# WeatherLightCoord.net
KiCad netlist of a schematic drawn in EAGLE
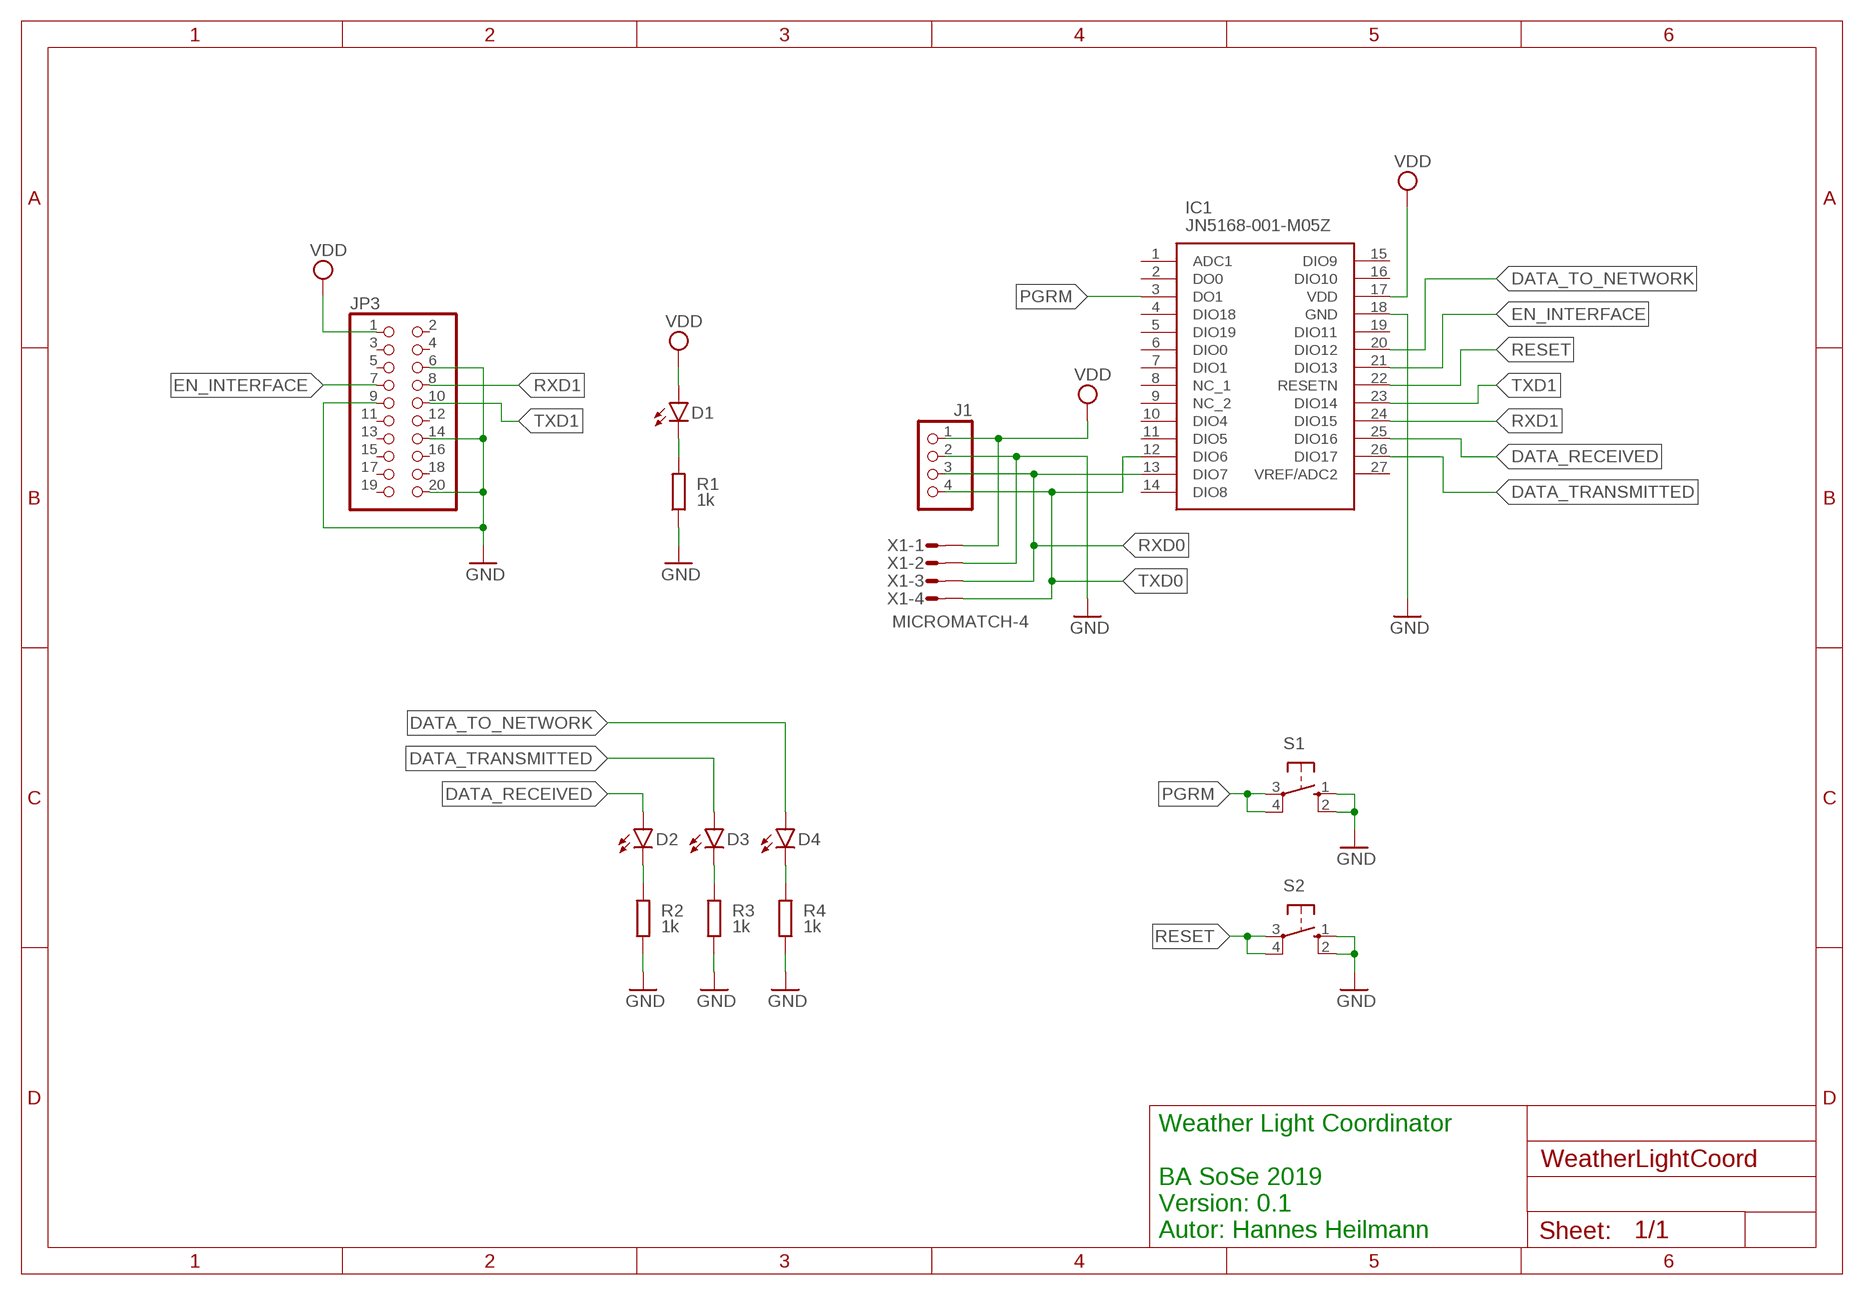
[diagram p0: schematic, sheet 1]

(export (version "E")
  (design (tool "Eeschema 10.0.6"))
  (components
    (comp (ref "D1")
      (value "LEDCHIPLED_1206")
      (footprint "eagle-import:CHIPLED_1206")
      (libsource (lib "eagle-import") (part "LEDCHIPLED_1206"))
    )
    (comp (ref "D2")
      (value "LEDCHIPLED_1206")
      (footprint "eagle-import:CHIPLED_1206")
      (libsource (lib "eagle-import") (part "LEDCHIPLED_1206"))
    )
    (comp (ref "D3")
      (value "LEDCHIPLED_1206")
      (footprint "eagle-import:CHIPLED_1206")
      (libsource (lib "eagle-import") (part "LEDCHIPLED_1206"))
    )
    (comp (ref "D4")
      (value "LEDCHIPLED_1206")
      (footprint "eagle-import:CHIPLED_1206")
      (libsource (lib "eagle-import") (part "LEDCHIPLED_1206"))
    )
    (comp (ref "IC1")
      (value "JN5168-001-M05Z")
      (footprint "eagle-import:JN5168001M05Z")
      (fields (field (name "MOUSER_PART_NUMBER") "771-JN5168-001-M05Z"))
      (libsource (lib "eagle-import") (part "JN5168-001-M05Z"))
    )
    (comp (ref "J1")
      (value "PINHD-1X4")
      (footprint "eagle-import:1X04")
      (libsource (lib "eagle-import") (part "PINHD-1X4"))
    )
    (comp (ref "JP3")
      (value "PINHD-2X10")
      (footprint "eagle-import:2X10")
      (libsource (lib "eagle-import") (part "PINHD-2X10"))
    )
    (comp (ref "R1")
      (value "1k")
      (footprint "eagle-import:R1206")
      (libsource (lib "eagle-import") (part "R-EU_R1206"))
    )
    (comp (ref "R2")
      (value "1k")
      (footprint "eagle-import:R1206")
      (libsource (lib "eagle-import") (part "R-EU_R1206"))
    )
    (comp (ref "R3")
      (value "1k")
      (footprint "eagle-import:R1206")
      (libsource (lib "eagle-import") (part "R-EU_R1206"))
    )
    (comp (ref "R4")
      (value "1k")
      (footprint "eagle-import:R1206")
      (libsource (lib "eagle-import") (part "R-EU_R1206"))
    )
    (comp (ref "S1")
      (value "10-XX")
      (footprint "eagle-import:B3F-10XX")
      (fields (field (name "MPN") "B3F-1000"))
      (libsource (lib "eagle-import") (part "10-XX"))
    )
    (comp (ref "S2")
      (value "10-XX")
      (footprint "eagle-import:B3F-10XX")
      (fields (field (name "MPN") "B3F-1000"))
      (libsource (lib "eagle-import") (part "10-XX"))
    )
    (comp (ref "X1")
      (value "MICROMATCH-4")
      (footprint "eagle-import:MICROMATCH-4")
      (fields (field (name "MPN") "7-215464-4"))
      (libsource (lib "eagle-import") (part "MICROMATCH-4"))
    )
  )
  (nets
    (net (code "1") (name "DATA_RECEIVED") (class "Default")
      (node (ref "D2") (pin "A") (pinfunction "A_A") (pintype "passive"))
      (node (ref "IC1") (pin "25") (pinfunction "DIO16_25") (pintype "bidirectional"))
    )
    (net (code "2") (name "DATA_TO_NETWORK") (class "Default")
      (node (ref "D4") (pin "A") (pinfunction "A_A") (pintype "passive"))
      (node (ref "IC1") (pin "20") (pinfunction "DIO12_20") (pintype "bidirectional"))
    )
    (net (code "3") (name "DATA_TRANSMITTED") (class "Default")
      (node (ref "D3") (pin "A") (pinfunction "A_A") (pintype "passive"))
      (node (ref "IC1") (pin "26") (pinfunction "DIO17_26") (pintype "bidirectional"))
    )
    (net (code "4") (name "EN_INTERFACE") (class "Default")
      (node (ref "IC1") (pin "21") (pinfunction "DIO13_21") (pintype "bidirectional"))
      (node (ref "JP3") (pin "7") (pinfunction "7_7") (pintype "passive"))
    )
    (net (code "5") (name "GND") (class "Default")
      (node (ref "IC1") (pin "18") (pinfunction "GND_18") (pintype "bidirectional"))
      (node (ref "J1") (pin "2") (pinfunction "2_2") (pintype "passive"))
      (node (ref "JP3") (pin "14") (pinfunction "14_14") (pintype "passive"))
      (node (ref "JP3") (pin "20") (pinfunction "20_20") (pintype "passive"))
      (node (ref "JP3") (pin "6") (pinfunction "6_6") (pintype "passive"))
      (node (ref "JP3") (pin "9") (pinfunction "9_9") (pintype "passive"))
      (node (ref "R1") (pin "1") (pinfunction "1_1") (pintype "passive"))
      (node (ref "R2") (pin "1") (pinfunction "1_1") (pintype "passive"))
      (node (ref "R3") (pin "1") (pinfunction "1_1") (pintype "passive"))
      (node (ref "R4") (pin "1") (pinfunction "1_1") (pintype "passive"))
      (node (ref "S1") (pin "1") (pinfunction "S_1") (pintype "passive"))
      (node (ref "S1") (pin "2") (pinfunction "S1_2") (pintype "passive"))
      (node (ref "S2") (pin "1") (pinfunction "S_1") (pintype "passive"))
      (node (ref "S2") (pin "2") (pinfunction "S1_2") (pintype "passive"))
      (node (ref "X1") (pin "2") (pinfunction "S_2") (pintype "passive"))
    )
    (net (code "6") (name "Net-(D1-PadC)") (class "Default")
      (node (ref "D1") (pin "C") (pinfunction "C_C") (pintype "passive"))
      (node (ref "R1") (pin "2") (pinfunction "2_2") (pintype "passive"))
    )
    (net (code "7") (name "Net-(D2-PadC)") (class "Default")
      (node (ref "D2") (pin "C") (pinfunction "C_C") (pintype "passive"))
      (node (ref "R2") (pin "2") (pinfunction "2_2") (pintype "passive"))
    )
    (net (code "8") (name "Net-(D3-PadC)") (class "Default")
      (node (ref "D3") (pin "C") (pinfunction "C_C") (pintype "passive"))
      (node (ref "R3") (pin "2") (pinfunction "2_2") (pintype "passive"))
    )
    (net (code "9") (name "Net-(D4-PadC)") (class "Default")
      (node (ref "D4") (pin "C") (pinfunction "C_C") (pintype "passive"))
      (node (ref "R4") (pin "2") (pinfunction "2_2") (pintype "passive"))
    )
    (net (code "10") (name "PGRM") (class "Default")
      (node (ref "IC1") (pin "3") (pinfunction "DO1_3") (pintype "bidirectional"))
      (node (ref "S1") (pin "3") (pinfunction "P_3") (pintype "passive"))
      (node (ref "S1") (pin "4") (pinfunction "P1_4") (pintype "passive"))
    )
    (net (code "11") (name "RESET") (class "Default")
      (node (ref "IC1") (pin "22") (pinfunction "RESETN_22") (pintype "bidirectional"))
      (node (ref "S2") (pin "3") (pinfunction "P_3") (pintype "passive"))
      (node (ref "S2") (pin "4") (pinfunction "P1_4") (pintype "passive"))
    )
    (net (code "12") (name "RXD0") (class "Default")
      (node (ref "IC1") (pin "13") (pinfunction "DIO7_13") (pintype "bidirectional"))
      (node (ref "J1") (pin "3") (pinfunction "3_3") (pintype "passive"))
      (node (ref "X1") (pin "3") (pinfunction "S_3") (pintype "passive"))
    )
    (net (code "13") (name "RXD1") (class "Default")
      (node (ref "IC1") (pin "24") (pinfunction "DIO15_24") (pintype "bidirectional"))
      (node (ref "JP3") (pin "8") (pinfunction "8_8") (pintype "passive"))
    )
    (net (code "14") (name "TXD0") (class "Default")
      (node (ref "IC1") (pin "12") (pinfunction "DIO6_12") (pintype "bidirectional"))
      (node (ref "J1") (pin "4") (pinfunction "4_4") (pintype "passive"))
      (node (ref "X1") (pin "4") (pinfunction "S_4") (pintype "passive"))
    )
    (net (code "15") (name "TXD1") (class "Default")
      (node (ref "IC1") (pin "23") (pinfunction "DIO14_23") (pintype "bidirectional"))
      (node (ref "JP3") (pin "10") (pinfunction "10_10") (pintype "passive"))
    )
    (net (code "16") (name "VDD") (class "Default")
      (node (ref "D1") (pin "A") (pinfunction "A_A") (pintype "passive"))
      (node (ref "IC1") (pin "17") (pinfunction "VDD_17") (pintype "bidirectional"))
      (node (ref "J1") (pin "1") (pinfunction "1_1") (pintype "passive"))
      (node (ref "JP3") (pin "1") (pinfunction "1_1") (pintype "passive"))
      (node (ref "X1") (pin "1") (pinfunction "S_1") (pintype "passive"))
    )
    (net (code "17") (name "unconnected-(IC1-ADC1-Pad1)") (class "Default")
      (node (ref "IC1") (pin "1") (pinfunction "ADC1_1") (pintype "bidirectional"))
    )
    (net (code "18") (name "unconnected-(IC1-DIO0-Pad6)") (class "Default")
      (node (ref "IC1") (pin "6") (pinfunction "DIO0_6") (pintype "bidirectional"))
    )
    (net (code "19") (name "unconnected-(IC1-DIO1-Pad7)") (class "Default")
      (node (ref "IC1") (pin "7") (pinfunction "DIO1_7") (pintype "bidirectional"))
    )
    (net (code "20") (name "unconnected-(IC1-DIO4-Pad10)") (class "Default")
      (node (ref "IC1") (pin "10") (pinfunction "DIO4_10") (pintype "bidirectional"))
    )
    (net (code "21") (name "unconnected-(IC1-DIO5-Pad11)") (class "Default")
      (node (ref "IC1") (pin "11") (pinfunction "DIO5_11") (pintype "bidirectional"))
    )
    (net (code "22") (name "unconnected-(IC1-DIO8-Pad14)") (class "Default")
      (node (ref "IC1") (pin "14") (pinfunction "DIO8_14") (pintype "bidirectional"))
    )
    (net (code "23") (name "unconnected-(IC1-DIO9-Pad15)") (class "Default")
      (node (ref "IC1") (pin "15") (pinfunction "DIO9_15") (pintype "bidirectional"))
    )
    (net (code "24") (name "unconnected-(IC1-DIO10-Pad16)") (class "Default")
      (node (ref "IC1") (pin "16") (pinfunction "DIO10_16") (pintype "bidirectional"))
    )
    (net (code "25") (name "unconnected-(IC1-DIO11-Pad19)") (class "Default")
      (node (ref "IC1") (pin "19") (pinfunction "DIO11_19") (pintype "bidirectional"))
    )
    (net (code "26") (name "unconnected-(IC1-DIO18-Pad4)") (class "Default")
      (node (ref "IC1") (pin "4") (pinfunction "DIO18_4") (pintype "bidirectional"))
    )
    (net (code "27") (name "unconnected-(IC1-DIO19-Pad5)") (class "Default")
      (node (ref "IC1") (pin "5") (pinfunction "DIO19_5") (pintype "bidirectional"))
    )
    (net (code "28") (name "unconnected-(IC1-DO0-Pad2)") (class "Default")
      (node (ref "IC1") (pin "2") (pinfunction "DO0_2") (pintype "bidirectional"))
    )
    (net (code "29") (name "unconnected-(IC1-NC_1-Pad8)") (class "Default")
      (node (ref "IC1") (pin "8") (pinfunction "NC_1_8") (pintype "bidirectional"))
    )
    (net (code "30") (name "unconnected-(IC1-NC_2-Pad9)") (class "Default")
      (node (ref "IC1") (pin "9") (pinfunction "NC_2_9") (pintype "bidirectional"))
    )
    (net (code "31") (name "unconnected-(IC1-VREF{slash}ADC2-Pad27)") (class "Default")
      (node (ref "IC1") (pin "27") (pinfunction "VREF/ADC2_27") (pintype "bidirectional"))
    )
    (net (code "32") (name "unconnected-(JP3-Pad2)") (class "Default")
      (node (ref "JP3") (pin "2") (pinfunction "2_2") (pintype "passive"))
    )
    (net (code "33") (name "unconnected-(JP3-Pad3)") (class "Default")
      (node (ref "JP3") (pin "3") (pinfunction "3_3") (pintype "passive"))
    )
    (net (code "34") (name "unconnected-(JP3-Pad4)") (class "Default")
      (node (ref "JP3") (pin "4") (pinfunction "4_4") (pintype "passive"))
    )
    (net (code "35") (name "unconnected-(JP3-Pad5)") (class "Default")
      (node (ref "JP3") (pin "5") (pinfunction "5_5") (pintype "passive"))
    )
    (net (code "36") (name "unconnected-(JP3-Pad11)") (class "Default")
      (node (ref "JP3") (pin "11") (pinfunction "11_11") (pintype "passive"))
    )
    (net (code "37") (name "unconnected-(JP3-Pad12)") (class "Default")
      (node (ref "JP3") (pin "12") (pinfunction "12_12") (pintype "passive"))
    )
    (net (code "38") (name "unconnected-(JP3-Pad13)") (class "Default")
      (node (ref "JP3") (pin "13") (pinfunction "13_13") (pintype "passive"))
    )
    (net (code "39") (name "unconnected-(JP3-Pad15)") (class "Default")
      (node (ref "JP3") (pin "15") (pinfunction "15_15") (pintype "passive"))
    )
    (net (code "40") (name "unconnected-(JP3-Pad16)") (class "Default")
      (node (ref "JP3") (pin "16") (pinfunction "16_16") (pintype "passive"))
    )
    (net (code "41") (name "unconnected-(JP3-Pad17)") (class "Default")
      (node (ref "JP3") (pin "17") (pinfunction "17_17") (pintype "passive"))
    )
    (net (code "42") (name "unconnected-(JP3-Pad18)") (class "Default")
      (node (ref "JP3") (pin "18") (pinfunction "18_18") (pintype "passive"))
    )
    (net (code "43") (name "unconnected-(JP3-Pad19)") (class "Default")
      (node (ref "JP3") (pin "19") (pinfunction "19_19") (pintype "passive"))
    )
  )
)
